# Power.net
KiCad netlist of a schematic drawn in Altium Designer
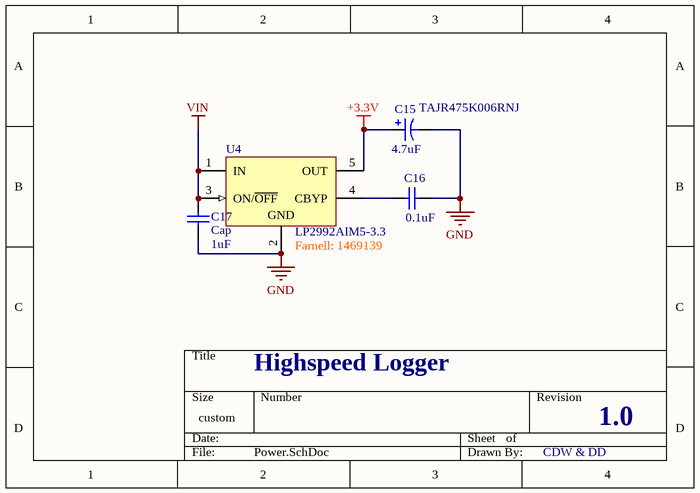
[diagram p0: Power.SchDoc]

(export (version "E")
  (design (tool "Eeschema 10.0.6"))
  (components
    (comp (ref "C15")
      (value "TAJR475K006RNJ")
      (footprint "0805")
      (description "Polarized Capacitor (Surface Mount)")
      (fields (field (name "ALTIUM_VALUE") "4.7uF") (field (name "PUBLISHER") "Altium Limited"))
      (libsource (lib "Miscellaneous Devices") (part "Cap Pol3"))
    )
    (comp (ref "C16")
      (value "0.1uF")
      (footprint "V0402")
      (description "Capacitor")
      (fields (field (name "Comment") "Cap") (field (name "PUBLISHER") "Altium Limited"))
      (libsource (lib "Miscellaneous Devices") (part "Cap"))
    )
    (comp (ref "C17")
      (value "Cap")
      (footprint "V0402")
      (description "Capacitor")
      (fields (field (name "ALTIUM_VALUE") "1uF") (field (name "PUBLISHER") "Altium Limited"))
      (libsource (lib "Miscellaneous Devices") (part "Cap"))
    )
    (comp (ref "U4")
      (value "LP2992AIM5-3.3")
      (footprint "MF05A_N")
      (description "Micropower 250 mA Low-Noise Ultra Low-Dropout Regulator, 5-pin SOT-23")
      (fields
        (field (name "MANUFACTURER") "National Semiconductor")
        (field (name "FARNELL") "1469139")
        (field (name "PUBLISHER") "Altium Limited")
      )
      (libsource (lib "NSC LDO") (part "LP2992AIM5-3.3"))
    )
  )
  (nets
    (net (code "1") (name "+3.3V") (class "Default")
      (node (ref "C15") (pin "1") (pinfunction "1_1") (pintype "passive"))
      (node (ref "U4") (pin "5") (pinfunction "OUT_5") (pintype "power_in"))
    )
    (net (code "2") (name "GND") (class "Default")
      (node (ref "C15") (pin "2") (pinfunction "2_2") (pintype "passive"))
      (node (ref "C16") (pin "2") (pinfunction "2_2") (pintype "passive"))
      (node (ref "C17") (pin "1") (pinfunction "1_1") (pintype "passive"))
      (node (ref "U4") (pin "2") (pinfunction "GND_2") (pintype "power_in"))
    )
    (net (code "3") (name "Net-(U4-CBYP)") (class "Default")
      (node (ref "C16") (pin "1") (pinfunction "1_1") (pintype "passive"))
      (node (ref "U4") (pin "4") (pinfunction "CBYP_4") (pintype "passive"))
    )
    (net (code "4") (name "VIN") (class "Default")
      (node (ref "C17") (pin "2") (pinfunction "2_2") (pintype "passive"))
      (node (ref "U4") (pin "1") (pinfunction "IN_1") (pintype "power_in"))
      (node (ref "U4") (pin "3") (pinfunction "ON/~{OFF}_3") (pintype "input"))
    )
  )
)
